# WL-STM.net
KiCad netlist of a schematic drawn in Altium Designer
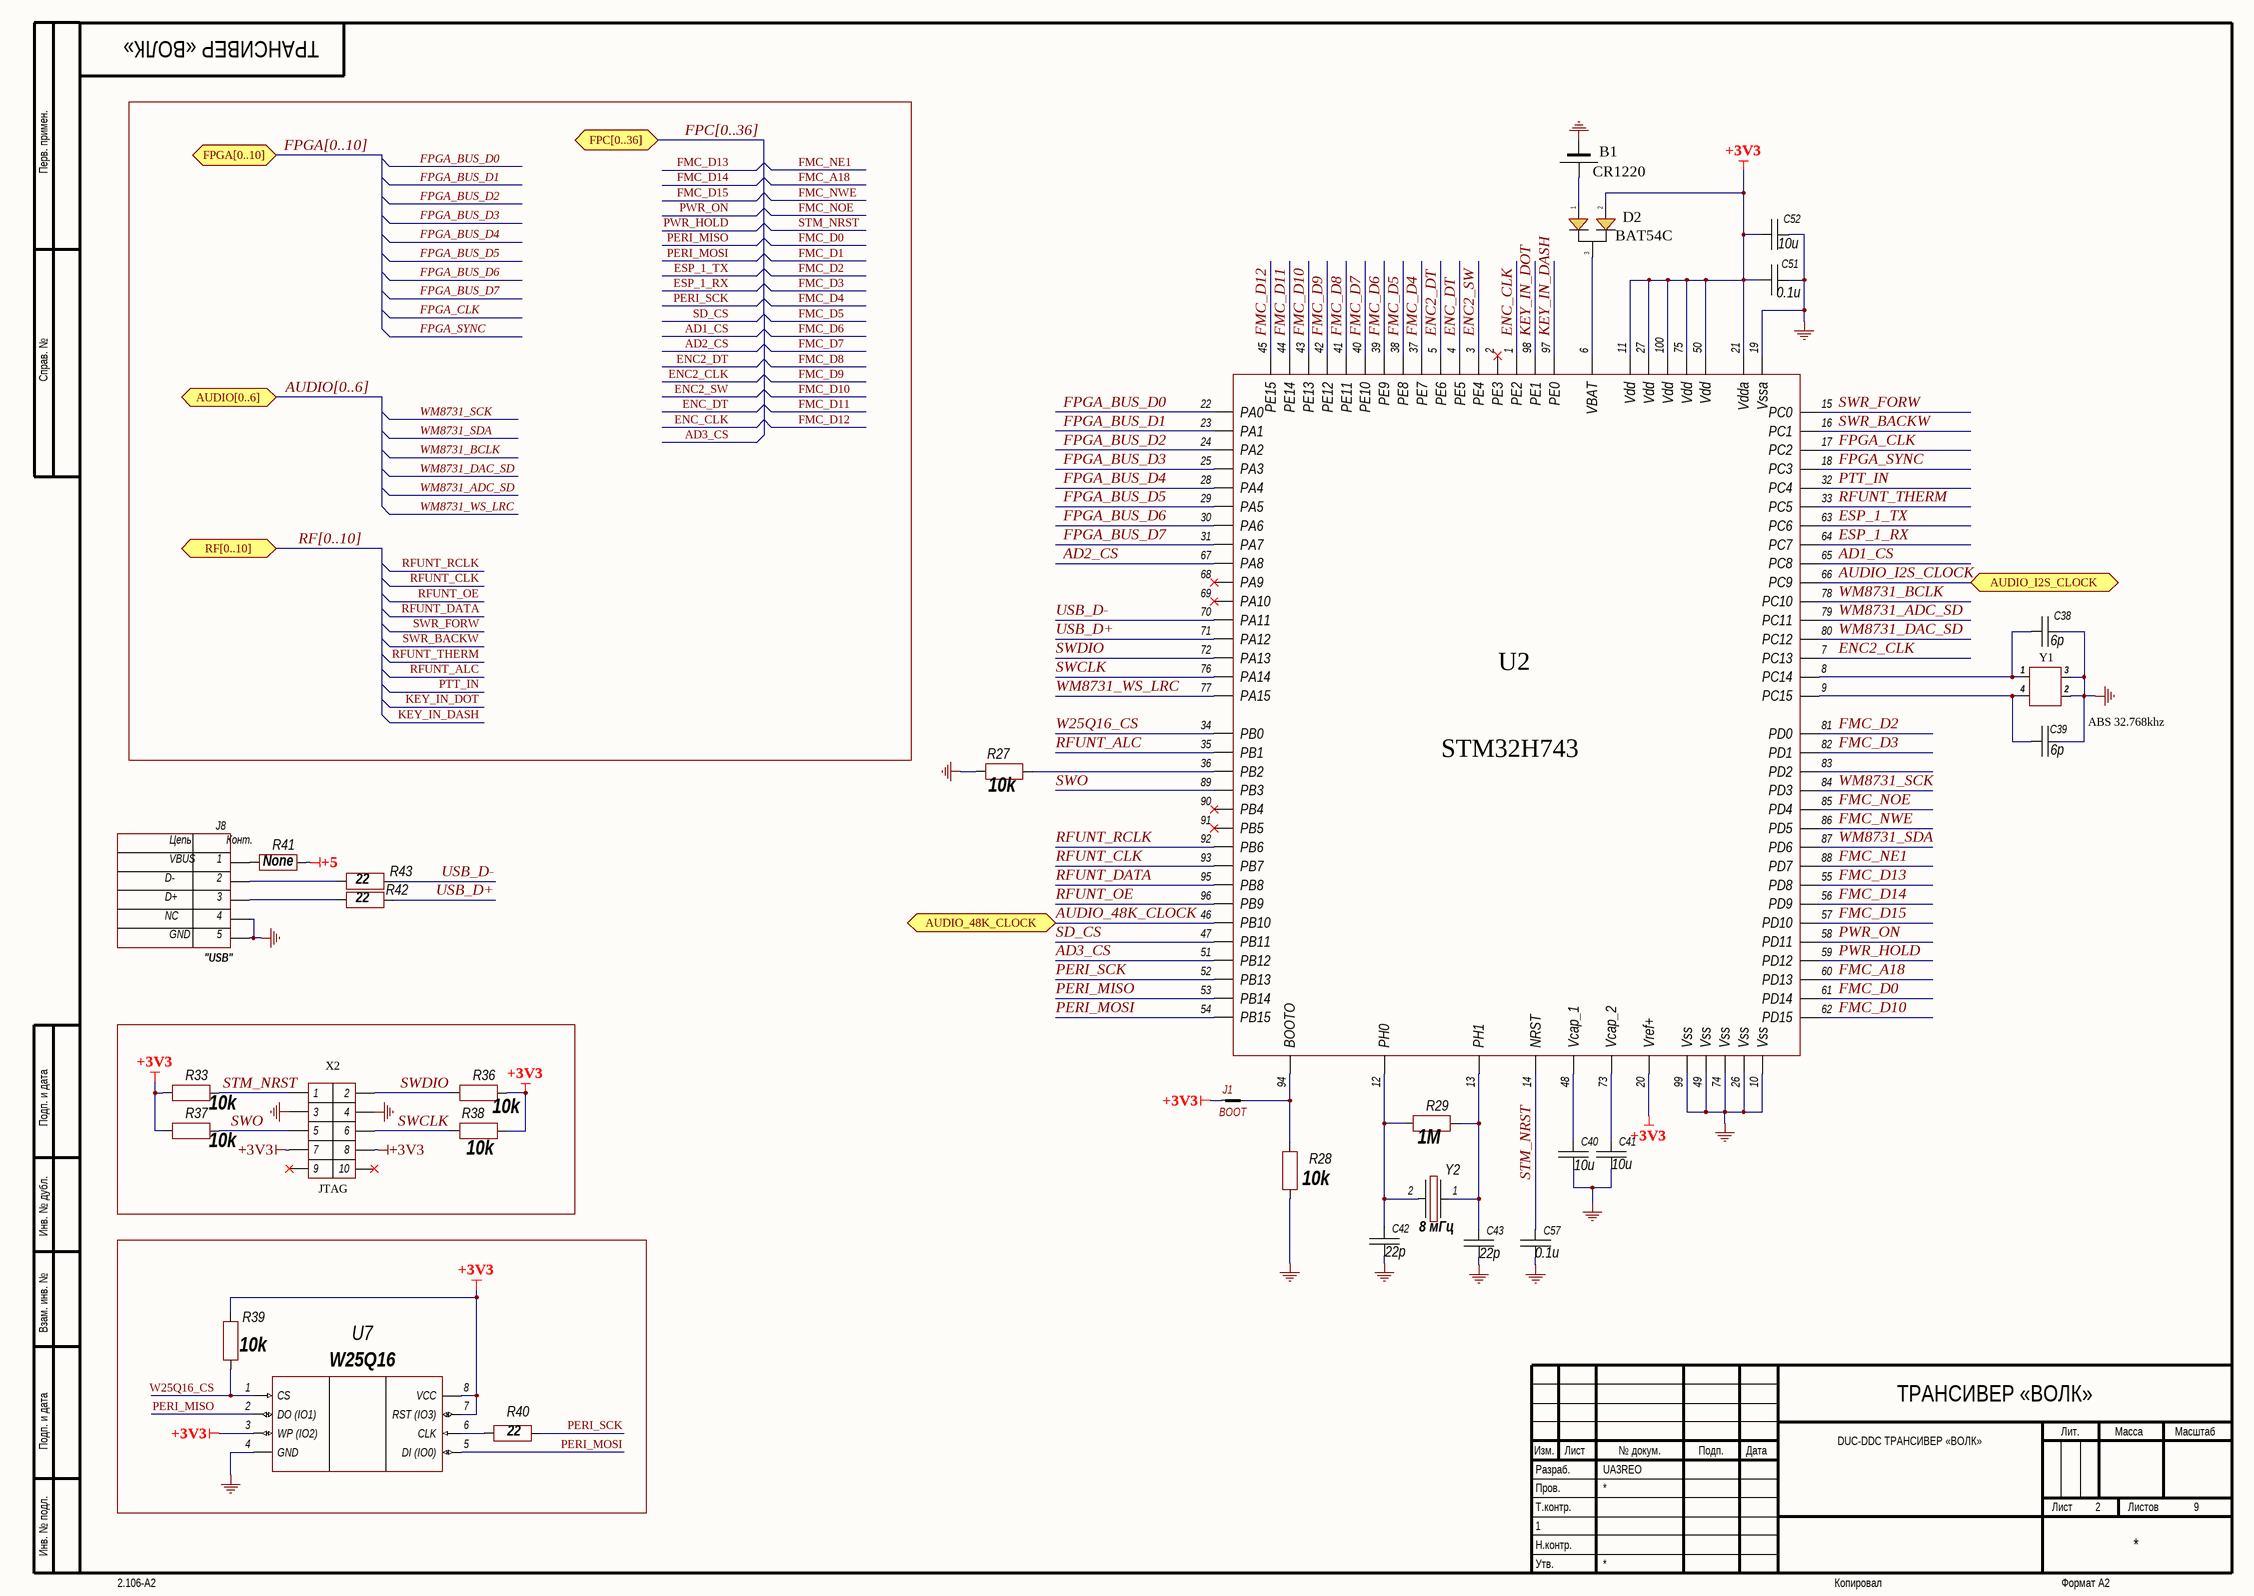
[diagram p0: WL-STM.SchDoc]

(export (version "E")
  (design (tool "Eeschema 10.0.6"))
  (components
    (comp (ref "B1") (value "CR1220") (footprint "CR2032") (libsource (lib "Connectors") (part "POWER_BAT")))
    (comp (ref "C38")
      (value "6p")
      (footprint "standard:CH0805C")
      (libsource (lib "Discrete") (part "Capacitor"))
    )
    (comp (ref "C39")
      (value "6p")
      (footprint "standard:CH0805C")
      (libsource (lib "Discrete") (part "Capacitor"))
    )
    (comp (ref "C40")
      (value "10u")
      (footprint "standard:CH0805C")
      (libsource (lib "Discrete") (part "Capacitor"))
    )
    (comp (ref "C41")
      (value "10u")
      (footprint "standard:CH0805C")
      (libsource (lib "Discrete") (part "Capacitor"))
    )
    (comp (ref "C42")
      (value "22p")
      (footprint "standard:CH0805C")
      (libsource (lib "Discrete") (part "Capacitor"))
    )
    (comp (ref "C43")
      (value "22p")
      (footprint "standard:CH0805C")
      (libsource (lib "Discrete") (part "Capacitor"))
    )
    (comp (ref "C51")
      (value "0.1u")
      (footprint "standard:CH0805C")
      (libsource (lib "Discrete") (part "Capacitor"))
    )
    (comp (ref "C52")
      (value "10u")
      (footprint "standard:CH0805C")
      (libsource (lib "Discrete") (part "Capacitor"))
    )
    (comp (ref "C57")
      (value "0.1u")
      (footprint "standard:CH0805C")
      (libsource (lib "Discrete") (part "Capacitor"))
    )
    (comp (ref "D2") (value "BAT54C") (footprint "SOT23_132") (libsource (lib "Analog") (part "BAT54C")))
    (comp (ref "J1") (value "BOOT") (footprint "CON: PLS-2") (libsource (lib "Analog") (part "DJAMPER")))
    (comp (ref "J8")
      (value "\"USB\"")
      (footprint "custom:CON: 0675031020")
      (description "USB")
      (libsource (lib "Connectors") (part "miniUSB-B"))
    )
    (comp (ref "R27")
      (value "10k")
      (footprint "standard:CH0805R")
      (libsource (lib "Discrete") (part "Resistor"))
    )
    (comp (ref "R28") (value "10k") (footprint "standard:CH0805R") (libsource (lib "") (part "Resistor_1")))
    (comp (ref "R29")
      (value "1M")
      (footprint "standard:CH0805R")
      (libsource (lib "Discrete") (part "Resistor"))
    )
    (comp (ref "R33")
      (value "10k")
      (footprint "standard:CH0805R")
      (libsource (lib "Discrete") (part "Resistor"))
    )
    (comp (ref "R36")
      (value "10k")
      (footprint "standard:CH0805R")
      (libsource (lib "Discrete") (part "Resistor"))
    )
    (comp (ref "R37")
      (value "10k")
      (footprint "standard:CH0805R")
      (libsource (lib "Discrete") (part "Resistor"))
    )
    (comp (ref "R38")
      (value "10k")
      (footprint "standard:CH0805R")
      (libsource (lib "Discrete") (part "Resistor"))
    )
    (comp (ref "R39") (value "10k") (footprint "standard:CH0805R") (libsource (lib "") (part "Resistor_1")))
    (comp (ref "R40") (value "22") (footprint "standard:CH0805R") (libsource (lib "") (part "Resistor_2")))
    (comp (ref "R41")
      (value "None")
      (footprint "standard:CH0805R")
      (libsource (lib "Discrete") (part "Resistor"))
    )
    (comp (ref "R42")
      (value "22")
      (footprint "standard:CH0805R")
      (libsource (lib "Discrete") (part "Resistor"))
    )
    (comp (ref "R43")
      (value "22")
      (footprint "standard:CH0805R")
      (libsource (lib "Discrete") (part "Resistor"))
    )
    (comp (ref "U2")
      (value "STM32H743")
      (footprint "100-LQFP")
      (libsource (lib "Digital") (part "STM32H743"))
    )
    (comp (ref "U7")
      (value "W25Q16")
      (footprint "SOIC-8-1")
      (description "Flash")
      (fields (field (name "MANUFACTURER") "Winbond Electronics"))
      (libsource (lib "Digital") (part "W25Q32JVZPIQ"))
    )
    (comp (ref "X2") (value "JTAG") (footprint "CON: PLD-10") (libsource (lib "Connectors") (part "Jtag")))
    (comp (ref "Y1") (value "ABS 32.768khz") (footprint "ABS-25") (libsource (lib "Discrete") (part "ABS25")))
    (comp (ref "Y2") (value "8 мГц") (footprint "OSC-dip") (libsource (lib "Discrete") (part "Oscillator")))
  )
  (nets
    (net (code "67") (name "+3V3") (class "Default")
      (node (ref "C51") (pin "1") (pinfunction "1_1") (pintype "power_in"))
      (node (ref "C52") (pin "1") (pinfunction "1_1") (pintype "power_in"))
      (node (ref "D2") (pin "2") (pinfunction "1_2") (pintype "passive"))
      (node (ref "J1") (pin "2") (pinfunction "2_2") (pintype "passive"))
      (node (ref "R33") (pin "2") (pinfunction "2_2") (pintype "passive"))
      (node (ref "R36") (pin "1") (pinfunction "1_1") (pintype "passive"))
      (node (ref "R37") (pin "2") (pinfunction "2_2") (pintype "passive"))
      (node (ref "R38") (pin "1") (pinfunction "1_1") (pintype "passive"))
      (node (ref "R39") (pin "2") (pinfunction "2_2") (pintype "passive"))
      (node (ref "U2") (pin "100") (pinfunction "Vdd_100") (pintype "power_in"))
      (node (ref "U2") (pin "11") (pinfunction "Vdd_11") (pintype "power_in"))
      (node (ref "U2") (pin "20") (pinfunction "Vref+_20") (pintype "power_in"))
      (node (ref "U2") (pin "21") (pinfunction "Vdda_21") (pintype "power_in"))
      (node (ref "U2") (pin "27") (pinfunction "Vdd_27") (pintype "power_in"))
      (node (ref "U2") (pin "50") (pinfunction "Vdd_50") (pintype "power_in"))
      (node (ref "U2") (pin "75") (pinfunction "Vdd_75") (pintype "power_in"))
      (node (ref "U7") (pin "3") (pinfunction "WP_(IO2)_3") (pintype "bidirectional"))
      (node (ref "U7") (pin "7") (pinfunction "RST_(IO3)_7") (pintype "bidirectional"))
      (node (ref "U7") (pin "8") (pinfunction "VCC_8") (pintype "power_in"))
      (node (ref "X2") (pin "7") (pinfunction "7_7") (pintype "power_in"))
      (node (ref "X2") (pin "8") (pinfunction "8_8") (pintype "power_in"))
    )
    (net (code "68") (name "+5") (class "Default")
      (node (ref "R41") (pin "1") (pinfunction "1_1") (pintype "passive"))
    )
    (net (code "69") (name "/AD1_CS") (class "Default")
      (node (ref "U2") (pin "65") (pinfunction "PC8_65") (pintype "power_in"))
    )
    (net (code "70") (name "/AD2_CS") (class "Default")
      (node (ref "U2") (pin "67") (pinfunction "PA8_67") (pintype "power_in"))
    )
    (net (code "71") (name "/AD3_CS") (class "Default")
      (node (ref "U2") (pin "51") (pinfunction "PB12_51") (pintype "power_in"))
    )
    (net (code "73") (name "/AUDIO_48K_CLOCK") (class "Default")
      (node (ref "U2") (pin "46") (pinfunction "PB10_46") (pintype "power_in"))
    )
    (net (code "74") (name "/AUDIO_I2S_CLOCK") (class "Default")
      (node (ref "U2") (pin "66") (pinfunction "PC9_66") (pintype "power_in"))
    )
    (net (code "75") (name "/ENC2_CLK") (class "Default")
      (node (ref "U2") (pin "7") (pinfunction "PC13_7") (pintype "power_in"))
    )
    (net (code "76") (name "/ENC2_DT") (class "Default")
      (node (ref "U2") (pin "5") (pinfunction "PE6_5") (pintype "power_in"))
    )
    (net (code "77") (name "/ENC2_SW") (class "Default")
      (node (ref "U2") (pin "3") (pinfunction "PE4_3") (pintype "power_in"))
    )
    (net (code "78") (name "/ENC_CLK") (class "Default")
      (node (ref "U2") (pin "1") (pinfunction "PE2_1") (pintype "power_in"))
    )
    (net (code "79") (name "/ENC_DT") (class "Default")
      (node (ref "U2") (pin "4") (pinfunction "PE5_4") (pintype "power_in"))
    )
    (net (code "80") (name "/ESP_1_RX") (class "Default")
      (node (ref "U2") (pin "64") (pinfunction "PC7_64") (pintype "power_in"))
    )
    (net (code "81") (name "/ESP_1_TX") (class "Default")
      (node (ref "U2") (pin "63") (pinfunction "PC6_63") (pintype "power_in"))
    )
    (net (code "82") (name "/FMC_A18") (class "Default")
      (node (ref "U2") (pin "60") (pinfunction "PD13_60") (pintype "power_in"))
    )
    (net (code "83") (name "/FMC_D0") (class "Default")
      (node (ref "U2") (pin "61") (pinfunction "PD14_61") (pintype "power_in"))
    )
    (net (code "85") (name "/FMC_D2") (class "Default")
      (node (ref "U2") (pin "81") (pinfunction "PD0_81") (pintype "power_in"))
    )
    (net (code "86") (name "/FMC_D3") (class "Default")
      (node (ref "U2") (pin "82") (pinfunction "PD1_82") (pintype "power_in"))
    )
    (net (code "87") (name "/FMC_D4") (class "Default")
      (node (ref "U2") (pin "37") (pinfunction "PE7_37") (pintype "power_in"))
    )
    (net (code "88") (name "/FMC_D5") (class "Default")
      (node (ref "U2") (pin "38") (pinfunction "PE8_38") (pintype "power_in"))
    )
    (net (code "89") (name "/FMC_D6") (class "Default")
      (node (ref "U2") (pin "39") (pinfunction "PE9_39") (pintype "power_in"))
    )
    (net (code "90") (name "/FMC_D7") (class "Default")
      (node (ref "U2") (pin "40") (pinfunction "PE10_40") (pintype "power_in"))
    )
    (net (code "91") (name "/FMC_D8") (class "Default")
      (node (ref "U2") (pin "41") (pinfunction "PE11_41") (pintype "power_in"))
    )
    (net (code "92") (name "/FMC_D9") (class "Default")
      (node (ref "U2") (pin "42") (pinfunction "PE12_42") (pintype "power_in"))
    )
    (net (code "93") (name "/FMC_D10") (class "Default")
      (node (ref "U2") (pin "43") (pinfunction "PE13_43") (pintype "power_in"))
      (node (ref "U2") (pin "62") (pinfunction "PD15_62") (pintype "power_in"))
    )
    (net (code "94") (name "/FMC_D11") (class "Default")
      (node (ref "U2") (pin "44") (pinfunction "PE14_44") (pintype "power_in"))
    )
    (net (code "95") (name "/FMC_D12") (class "Default")
      (node (ref "U2") (pin "45") (pinfunction "PE15_45") (pintype "power_in"))
    )
    (net (code "96") (name "/FMC_D13") (class "Default")
      (node (ref "U2") (pin "55") (pinfunction "PD8_55") (pintype "power_in"))
    )
    (net (code "97") (name "/FMC_D14") (class "Default")
      (node (ref "U2") (pin "56") (pinfunction "PD9_56") (pintype "power_in"))
    )
    (net (code "98") (name "/FMC_D15") (class "Default")
      (node (ref "U2") (pin "57") (pinfunction "PD10_57") (pintype "power_in"))
    )
    (net (code "99") (name "/FMC_NE1") (class "Default")
      (node (ref "U2") (pin "88") (pinfunction "PD7_88") (pintype "power_in"))
    )
    (net (code "100") (name "/FMC_NOE") (class "Default")
      (node (ref "U2") (pin "85") (pinfunction "PD4_85") (pintype "power_in"))
    )
    (net (code "101") (name "/FMC_NWE") (class "Default")
      (node (ref "U2") (pin "86") (pinfunction "PD5_86") (pintype "power_in"))
    )
    (net (code "104") (name "/FPGA_BUS_D0") (class "Default")
      (node (ref "U2") (pin "22") (pinfunction "PA0_22") (pintype "power_in"))
    )
    (net (code "105") (name "/FPGA_BUS_D1") (class "Default")
      (node (ref "U2") (pin "23") (pinfunction "PA1_23") (pintype "power_in"))
    )
    (net (code "106") (name "/FPGA_BUS_D2") (class "Default")
      (node (ref "U2") (pin "24") (pinfunction "PA2_24") (pintype "power_in"))
    )
    (net (code "107") (name "/FPGA_BUS_D3") (class "Default")
      (node (ref "U2") (pin "25") (pinfunction "PA3_25") (pintype "power_in"))
    )
    (net (code "108") (name "/FPGA_BUS_D4") (class "Default")
      (node (ref "U2") (pin "28") (pinfunction "PA4_28") (pintype "power_in"))
    )
    (net (code "109") (name "/FPGA_BUS_D5") (class "Default")
      (node (ref "U2") (pin "29") (pinfunction "PA5_29") (pintype "power_in"))
    )
    (net (code "110") (name "/FPGA_BUS_D6") (class "Default")
      (node (ref "U2") (pin "30") (pinfunction "PA6_30") (pintype "power_in"))
    )
    (net (code "111") (name "/FPGA_BUS_D7") (class "Default")
      (node (ref "U2") (pin "31") (pinfunction "PA7_31") (pintype "power_in"))
    )
    (net (code "112") (name "/FPGA_CLK") (class "Default")
      (node (ref "U2") (pin "17") (pinfunction "PC2_17") (pintype "power_in"))
    )
    (net (code "113") (name "/FPGA_SYNC") (class "Default")
      (node (ref "U2") (pin "18") (pinfunction "PC3_18") (pintype "power_in"))
    )
    (net (code "114") (name "/KEY_IN_DASH") (class "Default")
      (node (ref "U2") (pin "97") (pinfunction "PE0_97") (pintype "power_in"))
    )
    (net (code "115") (name "/KEY_IN_DOT") (class "Default")
      (node (ref "U2") (pin "98") (pinfunction "PE1_98") (pintype "power_in"))
    )
    (net (code "116") (name "/PERI_MISO") (class "Default")
      (node (ref "U2") (pin "53") (pinfunction "PB14_53") (pintype "power_in"))
      (node (ref "U7") (pin "2") (pinfunction "DO_(IO1)_2") (pintype "bidirectional"))
    )
    (net (code "117") (name "/PERI_MOSI") (class "Default")
      (node (ref "U2") (pin "54") (pinfunction "PB15_54") (pintype "power_in"))
      (node (ref "U7") (pin "5") (pinfunction "DI_(IO0)_5") (pintype "bidirectional"))
    )
    (net (code "118") (name "/PERI_SCK") (class "Default")
      (node (ref "R40") (pin "2") (pinfunction "2_2") (pintype "passive"))
      (node (ref "U2") (pin "52") (pinfunction "PB13_52") (pintype "power_in"))
    )
    (net (code "119") (name "/PTT_IN") (class "Default")
      (node (ref "U2") (pin "32") (pinfunction "PC4_32") (pintype "power_in"))
    )
    (net (code "120") (name "/PWR_HOLD") (class "Default")
      (node (ref "U2") (pin "59") (pinfunction "PD12_59") (pintype "power_in"))
    )
    (net (code "121") (name "/PWR_ON") (class "Default")
      (node (ref "U2") (pin "58") (pinfunction "PD11_58") (pintype "power_in"))
    )
    (net (code "122") (name "/RFUNT_ALC") (class "Default")
      (node (ref "U2") (pin "35") (pinfunction "PB1_35") (pintype "power_in"))
    )
    (net (code "123") (name "/RFUNT_CLK") (class "Default")
      (node (ref "U2") (pin "93") (pinfunction "PB7_93") (pintype "power_in"))
    )
    (net (code "124") (name "/RFUNT_DATA") (class "Default")
      (node (ref "U2") (pin "95") (pinfunction "PB8_95") (pintype "power_in"))
    )
    (net (code "125") (name "/RFUNT_OE") (class "Default")
      (node (ref "U2") (pin "96") (pinfunction "PB9_96") (pintype "power_in"))
    )
    (net (code "126") (name "/RFUNT_RCLK") (class "Default")
      (node (ref "U2") (pin "92") (pinfunction "PB6_92") (pintype "power_in"))
    )
    (net (code "127") (name "/RFUNT_THERM") (class "Default")
      (node (ref "U2") (pin "33") (pinfunction "PC5_33") (pintype "power_in"))
    )
    (net (code "129") (name "/SD_CS") (class "Default")
      (node (ref "U2") (pin "47") (pinfunction "PB11_47") (pintype "power_in"))
    )
    (net (code "130") (name "/STM_NRST") (class "Default")
      (node (ref "C57") (pin "2") (pinfunction "2_2") (pintype "power_in"))
      (node (ref "U2") (pin "14") (pinfunction "NRST_14") (pintype "power_in"))
    )
    (net (code "131") (name "/SWCLK") (class "Default")
      (node (ref "R38") (pin "2") (pinfunction "2_2") (pintype "passive"))
      (node (ref "U2") (pin "76") (pinfunction "PA14_76") (pintype "power_in"))
      (node (ref "X2") (pin "6") (pinfunction "6_6") (pintype "power_in"))
    )
    (net (code "132") (name "/SWDIO") (class "Default")
      (node (ref "R36") (pin "2") (pinfunction "2_2") (pintype "passive"))
      (node (ref "U2") (pin "72") (pinfunction "PA13_72") (pintype "power_in"))
      (node (ref "X2") (pin "2") (pinfunction "2_2") (pintype "power_in"))
    )
    (net (code "133") (name "/SWO") (class "Default")
      (node (ref "R37") (pin "1") (pinfunction "1_1") (pintype "passive"))
      (node (ref "U2") (pin "89") (pinfunction "PB3_89") (pintype "power_in"))
      (node (ref "X2") (pin "5") (pinfunction "5_5") (pintype "power_in"))
    )
    (net (code "134") (name "/SWR_BACKW") (class "Default")
      (node (ref "U2") (pin "16") (pinfunction "PC1_16") (pintype "power_in"))
    )
    (net (code "135") (name "/SWR_FORW") (class "Default")
      (node (ref "U2") (pin "15") (pinfunction "PC0_15") (pintype "power_in"))
    )
    (net (code "136") (name "/USB_D+") (class "Default")
      (node (ref "R42") (pin "1") (pinfunction "1_1") (pintype "passive"))
      (node (ref "U2") (pin "71") (pinfunction "PA12_71") (pintype "power_in"))
    )
    (net (code "137") (name "/USB_D-") (class "Default")
      (node (ref "R43") (pin "1") (pinfunction "1_1") (pintype "passive"))
      (node (ref "U2") (pin "70") (pinfunction "PA11_70") (pintype "power_in"))
    )
    (net (code "138") (name "/W25Q16_CS") (class "Default")
      (node (ref "R39") (pin "1") (pinfunction "1_1") (pintype "passive"))
      (node (ref "U2") (pin "34") (pinfunction "PB0_34") (pintype "power_in"))
      (node (ref "U7") (pin "1") (pinfunction "CS_1") (pintype "input"))
    )
    (net (code "139") (name "/WM8731_ADC_SD") (class "Default")
      (node (ref "U2") (pin "79") (pinfunction "PC11_79") (pintype "power_in"))
    )
    (net (code "140") (name "/WM8731_BCLK") (class "Default")
      (node (ref "U2") (pin "78") (pinfunction "PC10_78") (pintype "power_in"))
    )
    (net (code "141") (name "/WM8731_DAC_SD") (class "Default")
      (node (ref "U2") (pin "80") (pinfunction "PC12_80") (pintype "power_in"))
    )
    (net (code "142") (name "/WM8731_SCK") (class "Default")
      (node (ref "U2") (pin "84") (pinfunction "PD3_84") (pintype "power_in"))
    )
    (net (code "143") (name "/WM8731_SDA") (class "Default")
      (node (ref "U2") (pin "87") (pinfunction "PD6_87") (pintype "power_in"))
    )
    (net (code "144") (name "/WM8731_WS_LRC") (class "Default")
      (node (ref "U2") (pin "77") (pinfunction "PA15_77") (pintype "power_in"))
    )
    (net (code "145") (name "GND") (class "Default")
      (node (ref "B1") (pin "2") (pinfunction "1_2") (pintype "passive"))
      (node (ref "C38") (pin "2") (pinfunction "2_2") (pintype "power_in"))
      (node (ref "C39") (pin "2") (pinfunction "2_2") (pintype "power_in"))
      (node (ref "C40") (pin "1") (pinfunction "1_1") (pintype "power_in"))
      (node (ref "C41") (pin "1") (pinfunction "1_1") (pintype "power_in"))
      (node (ref "C42") (pin "1") (pinfunction "1_1") (pintype "power_in"))
      (node (ref "C43") (pin "1") (pinfunction "1_1") (pintype "power_in"))
      (node (ref "C51") (pin "2") (pinfunction "2_2") (pintype "power_in"))
      (node (ref "C52") (pin "2") (pinfunction "2_2") (pintype "power_in"))
      (node (ref "C57") (pin "1") (pinfunction "1_1") (pintype "power_in"))
      (node (ref "J8") (pin "4") (pinfunction "4_4") (pintype "passive"))
      (node (ref "J8") (pin "5") (pinfunction "5_5") (pintype "passive"))
      (node (ref "R27") (pin "2") (pinfunction "2_2") (pintype "passive"))
      (node (ref "R28") (pin "1") (pinfunction "1_1") (pintype "passive"))
      (node (ref "U2") (pin "10") (pinfunction "Vss_10") (pintype "power_in"))
      (node (ref "U2") (pin "19") (pinfunction "Vssa_19") (pintype "power_in"))
      (node (ref "U2") (pin "26") (pinfunction "Vss_26") (pintype "power_in"))
      (node (ref "U2") (pin "49") (pinfunction "Vss_49") (pintype "power_in"))
      (node (ref "U2") (pin "74") (pinfunction "Vss_74") (pintype "power_in"))
      (node (ref "U2") (pin "99") (pinfunction "Vss_99") (pintype "power_in"))
      (node (ref "U7") (pin "4") (pinfunction "GND_4") (pintype "power_in"))
      (node (ref "X2") (pin "3") (pinfunction "3_3") (pintype "passive"))
      (node (ref "X2") (pin "4") (pinfunction "4_4") (pintype "power_in"))
      (node (ref "Y1") (pin "2") (pinfunction "2_2") (pintype "passive"))
      (node (ref "Y1") (pin "3") (pinfunction "3_3") (pintype "passive"))
    )
    (net (code "146") (name "Net-(B1-0)") (class "Default")
      (node (ref "B1") (pin "1") (pinfunction "0_1") (pintype "passive"))
      (node (ref "D2") (pin "1") (pinfunction "1_1") (pintype "passive"))
    )
    (net (code "147") (name "Net-(J8-Pad1)") (class "Default")
      (node (ref "J8") (pin "1") (pintype "passive"))
      (node (ref "R41") (pin "2") (pinfunction "2_2") (pintype "passive"))
    )
    (net (code "148") (name "Net-(J8-Pad2)") (class "Default")
      (node (ref "J8") (pin "2") (pinfunction "2_2") (pintype "passive"))
      (node (ref "R43") (pin "2") (pinfunction "2_2") (pintype "passive"))
    )
    (net (code "149") (name "Net-(J8-Pad3)") (class "Default")
      (node (ref "J8") (pin "3") (pinfunction "3_3") (pintype "passive"))
      (node (ref "R42") (pin "2") (pinfunction "2_2") (pintype "passive"))
    )
    (net (code "150") (name "Net-(R33-Pad1)") (class "Default")
      (node (ref "R33") (pin "1") (pinfunction "1_1") (pintype "passive"))
      (node (ref "X2") (pin "1") (pinfunction "1_1") (pintype "passive"))
    )
    (net (code "151") (name "Net-(U2-BOOTO)") (class "Default")
      (node (ref "J1") (pin "1") (pinfunction "1_1") (pintype "passive"))
      (node (ref "R28") (pin "2") (pinfunction "2_2") (pintype "passive"))
      (node (ref "U2") (pin "94") (pinfunction "BOOTO_94") (pintype "power_in"))
    )
    (net (code "152") (name "Net-(U2-PB2)") (class "Default")
      (node (ref "R27") (pin "1") (pinfunction "1_1") (pintype "passive"))
      (node (ref "U2") (pin "36") (pinfunction "PB2_36") (pintype "power_in"))
    )
    (net (code "153") (name "Net-(U2-PC14)") (class "Default")
      (node (ref "C38") (pin "1") (pinfunction "1_1") (pintype "power_in"))
      (node (ref "U2") (pin "8") (pinfunction "PC14_8") (pintype "power_in"))
      (node (ref "Y1") (pin "1") (pinfunction "1_1") (pintype "passive"))
    )
    (net (code "154") (name "Net-(U2-PC15)") (class "Default")
      (node (ref "C39") (pin "1") (pinfunction "1_1") (pintype "power_in"))
      (node (ref "U2") (pin "9") (pinfunction "PC15_9") (pintype "power_in"))
      (node (ref "Y1") (pin "4") (pinfunction "4_4") (pintype "passive"))
    )
    (net (code "155") (name "Net-(U2-PH0)") (class "Default")
      (node (ref "C42") (pin "2") (pinfunction "2_2") (pintype "power_in"))
      (node (ref "R29") (pin "2") (pinfunction "2_2") (pintype "passive"))
      (node (ref "U2") (pin "12") (pinfunction "PH0_12") (pintype "power_in"))
      (node (ref "Y2") (pin "2") (pinfunction "2_2") (pintype "passive"))
    )
    (net (code "156") (name "Net-(U2-PH1)") (class "Default")
      (node (ref "C43") (pin "2") (pinfunction "2_2") (pintype "power_in"))
      (node (ref "R29") (pin "1") (pinfunction "1_1") (pintype "passive"))
      (node (ref "U2") (pin "13") (pinfunction "PH1_13") (pintype "power_in"))
      (node (ref "Y2") (pin "1") (pinfunction "1_1") (pintype "passive"))
    )
    (net (code "157") (name "Net-(U2-VBAT)") (class "Default")
      (node (ref "D2") (pin "3") (pinfunction "3_3") (pintype "passive"))
      (node (ref "U2") (pin "6") (pinfunction "VBAT_6") (pintype "power_in"))
    )
    (net (code "158") (name "Net-(U2-Vcap_1)") (class "Default")
      (node (ref "C40") (pin "2") (pinfunction "2_2") (pintype "power_in"))
      (node (ref "U2") (pin "48") (pinfunction "Vcap_1_48") (pintype "power_in"))
    )
    (net (code "159") (name "Net-(U2-Vcap_2)") (class "Default")
      (node (ref "C41") (pin "2") (pinfunction "2_2") (pintype "power_in"))
      (node (ref "U2") (pin "73") (pinfunction "Vcap_2_73") (pintype "power_in"))
    )
    (net (code "160") (name "Net-(U7-CLK)") (class "Default")
      (node (ref "R40") (pin "1") (pinfunction "1_1") (pintype "passive"))
      (node (ref "U7") (pin "6") (pinfunction "CLK_6") (pintype "input"))
    )
    (net (code "161") (name "unconnected-(U2-PA9-Pad68)") (class "Default")
      (node (ref "U2") (pin "68") (pinfunction "PA9_68") (pintype "power_in+no_connect"))
    )
    (net (code "162") (name "unconnected-(U2-PA10-Pad69)") (class "Default")
      (node (ref "U2") (pin "69") (pinfunction "PA10_69") (pintype "power_in+no_connect"))
    )
    (net (code "163") (name "unconnected-(U2-PB4-Pad90)") (class "Default")
      (node (ref "U2") (pin "90") (pinfunction "PB4_90") (pintype "power_in+no_connect"))
    )
    (net (code "164") (name "unconnected-(U2-PB5-Pad91)") (class "Default")
      (node (ref "U2") (pin "91") (pinfunction "PB5_91") (pintype "power_in+no_connect"))
    )
    (net (code "165") (name "unconnected-(U2-PD2-Pad83)") (class "Default")
      (node (ref "U2") (pin "83") (pinfunction "PD2_83") (pintype "power_in"))
    )
    (net (code "166") (name "unconnected-(U2-PE3-Pad2)") (class "Default")
      (node (ref "U2") (pin "2") (pinfunction "PE3_2") (pintype "power_in+no_connect"))
    )
    (net (code "167") (name "unconnected-(X2-Pad9)") (class "Default")
      (node (ref "X2") (pin "9") (pinfunction "9_9") (pintype "power_in+no_connect"))
    )
    (net (code "168") (name "unconnected-(X2-Pad10)") (class "Default")
      (node (ref "X2") (pin "10") (pinfunction "10_10") (pintype "power_in+no_connect"))
    )
  )
)
